# board_One.net
KiCad netlist of a schematic drawn in Altium Designer
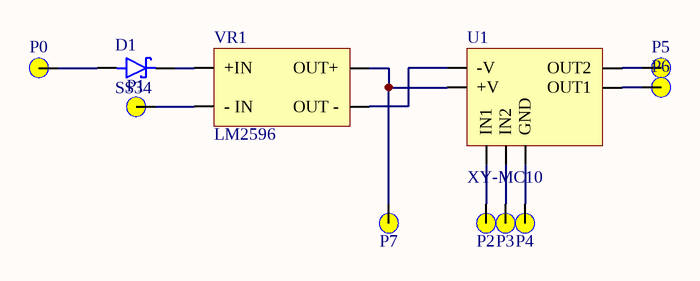
[diagram p0: board_One.SchDoc]

(export (version "E")
  (design (tool "Eeschema 10.0.6"))
  (components
    (comp (ref "D1")
      (value "SS34")
      (footprint "DIOM7959X265N")
      (description "SS34 - діод Шоттки")
      (fields (field (name "MF") "onsemi"))
      (libsource (lib "Sch_SS34") (part "Diode_SS34"))
    )
    (comp (ref "P0") (value "PIN_1") (footprint "PCB_Pin_1") (libsource (lib "Sch_Pin_1") (part "PIN_1")))
    (comp (ref "P1") (value "PIN_1") (footprint "PCB_Pin_1") (libsource (lib "Sch_Pin_1") (part "PIN_1")))
    (comp (ref "P2") (value "PIN_1") (footprint "PCB_Pin_1") (libsource (lib "Sch_Pin_1") (part "PIN_1")))
    (comp (ref "P3") (value "PIN_1") (footprint "PCB_Pin_1") (libsource (lib "Sch_Pin_1") (part "PIN_1")))
    (comp (ref "P4") (value "PIN_1") (footprint "PCB_Pin_1") (libsource (lib "Sch_Pin_1") (part "PIN_1")))
    (comp (ref "P5") (value "PIN_1") (footprint "PCB_Pin_1") (libsource (lib "Sch_Pin_1") (part "PIN_1")))
    (comp (ref "P6") (value "PIN_1") (footprint "PCB_Pin_1") (libsource (lib "Sch_Pin_1") (part "PIN_1")))
    (comp (ref "P7") (value "PIN_1") (footprint "PCB_Pin_1") (libsource (lib "Sch_Pin_1") (part "PIN_1")))
    (comp (ref "U1")
      (value "XY-MC10")
      (footprint "PCB_XY-MC10")
      (libsource (lib "Sch_XY-MC10") (part "XY-MC10"))
    )
    (comp (ref "VR1")
      (value "LM2596")
      (footprint "DC-DC Step-Down Footprint")
      (description "DC-DC конвертер знижуючий 4.5...40В на 1.5...35В на LM2596")
      (libsource (lib "Sch_LM2596") (part "DC-DC Step-Down"))
    )
  )
  (nets
    (net (code "1") (name "Net-(D1-K)") (class "Default")
      (node (ref "D1") (pin "C") (pinfunction "K_C") (pintype "passive"))
      (node (ref "VR1") (pin "1") (pinfunction "+IN_1") (pintype "power_in"))
    )
    (net (code "2") (name "Net-(P0-Pin)") (class "Default")
      (node (ref "D1") (pin "A") (pinfunction "A_A") (pintype "passive"))
      (node (ref "P0") (pin "0") (pinfunction "Pin_0") (pintype "passive"))
    )
    (net (code "3") (name "Net-(P1-Pin)") (class "Default")
      (node (ref "P1") (pin "0") (pinfunction "Pin_0") (pintype "passive"))
      (node (ref "VR1") (pin "0") (pinfunction "-_IN_0") (pintype "power_in"))
    )
    (net (code "4") (name "Net-(P2-Pin)") (class "Default")
      (node (ref "P2") (pin "0") (pinfunction "Pin_0") (pintype "passive"))
      (node (ref "U1") (pin "2") (pinfunction "IN1_2") (pintype "passive"))
    )
    (net (code "5") (name "Net-(P3-Pin)") (class "Default")
      (node (ref "P3") (pin "0") (pinfunction "Pin_0") (pintype "passive"))
      (node (ref "U1") (pin "3") (pinfunction "IN2_3") (pintype "passive"))
    )
    (net (code "6") (name "Net-(P4-Pin)") (class "Default")
      (node (ref "P4") (pin "0") (pinfunction "Pin_0") (pintype "passive"))
      (node (ref "U1") (pin "4") (pinfunction "GND_4") (pintype "passive"))
    )
    (net (code "7") (name "Net-(P5-Pin)") (class "Default")
      (node (ref "P5") (pin "0") (pinfunction "Pin_0") (pintype "passive"))
      (node (ref "U1") (pin "6") (pinfunction "OUT2_6") (pintype "passive"))
    )
    (net (code "8") (name "Net-(P6-Pin)") (class "Default")
      (node (ref "P6") (pin "0") (pinfunction "Pin_0") (pintype "passive"))
      (node (ref "U1") (pin "5") (pinfunction "OUT1_5") (pintype "passive"))
    )
    (net (code "9") (name "Net-(P7-Pin)") (class "Default")
      (node (ref "P7") (pin "0") (pinfunction "Pin_0") (pintype "passive"))
      (node (ref "U1") (pin "1") (pinfunction "+V_1") (pintype "passive"))
      (node (ref "VR1") (pin "2") (pinfunction "OUT+_2") (pintype "power_in"))
    )
    (net (code "10") (name "Net-(U1--V)") (class "Default")
      (node (ref "U1") (pin "0") (pinfunction "-V_0") (pintype "passive"))
      (node (ref "VR1") (pin "3") (pinfunction "OUT_-_3") (pintype "power_in"))
    )
  )
)
